# 03-LED-GREEN.net
KiCad netlist of a schematic drawn in Altium Designer
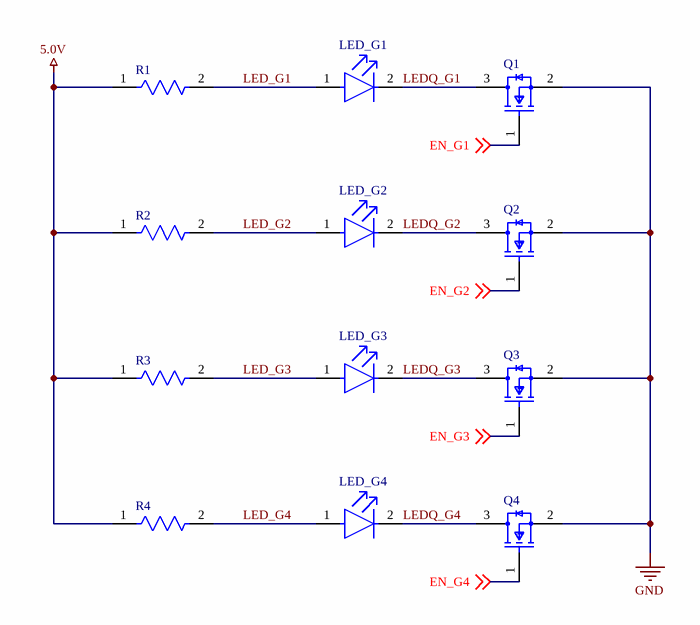
[diagram p0: 03-LED-GREEN.SchDoc]

(export (version "E")
  (design (tool "Eeschema 10.0.6"))
  (components
    (comp (ref "LED_G1")
      (value "SML-LX1206GC-TR")
      (footprint "FP-SML-LX1206GC-TR-MFG")
      (description "LED GREEN CLEAR 1206 SMD")
      (libsource (lib "Altium Content Vault") (part "ab1c01a81903e929fc6c44469aada92"))
    )
    (comp (ref "LED_G2")
      (value "SML-LX1206GC-TR")
      (footprint "FP-SML-LX1206GC-TR-MFG")
      (description "LED GREEN CLEAR 1206 SMD")
      (libsource (lib "Altium Content Vault") (part "ab1c01a81903e929fc6c44469aada92"))
    )
    (comp (ref "LED_G3")
      (value "SML-LX1206GC-TR")
      (footprint "FP-SML-LX1206GC-TR-MFG")
      (description "LED GREEN CLEAR 1206 SMD")
      (libsource (lib "Altium Content Vault") (part "ab1c01a81903e929fc6c44469aada92"))
    )
    (comp (ref "LED_G4")
      (value "SML-LX1206GC-TR")
      (footprint "FP-SML-LX1206GC-TR-MFG")
      (description "LED GREEN CLEAR 1206 SMD")
      (libsource (lib "Altium Content Vault") (part "ab1c01a81903e929fc6c44469aada92"))
    )
    (comp (ref "Q1")
      (value "2N7002-7-F")
      (footprint "FP-SOT23-MFG")
      (description "MOSFET N-CH 60V 115MA SOT23-3")
      (fields (field (name "VOLTAGE") "60V"))
      (libsource (lib "Altium Content Vault") (part "3b9c635fedb024a5347a57b145af9cc"))
    )
    (comp (ref "Q2")
      (value "2N7002-7-F")
      (footprint "FP-SOT23-MFG")
      (description "MOSFET N-CH 60V 115MA SOT23-3")
      (fields (field (name "VOLTAGE") "60V"))
      (libsource (lib "Altium Content Vault") (part "3b9c635fedb024a5347a57b145af9cc"))
    )
    (comp (ref "Q3")
      (value "2N7002-7-F")
      (footprint "FP-SOT23-MFG")
      (description "MOSFET N-CH 60V 115MA SOT23-3")
      (fields (field (name "VOLTAGE") "60V"))
      (libsource (lib "Altium Content Vault") (part "3b9c635fedb024a5347a57b145af9cc"))
    )
    (comp (ref "Q4")
      (value "2N7002-7-F")
      (footprint "FP-SOT23-MFG")
      (description "MOSFET N-CH 60V 115MA SOT23-3")
      (fields (field (name "VOLTAGE") "60V"))
      (libsource (lib "Altium Content Vault") (part "3b9c635fedb024a5347a57b145af9cc"))
    )
    (comp (ref "R1")
      (value "CRCW1206330RFKEA")
      (footprint "FP-CRCW1206-e3-IPC_A")
      (description "RES Thick Film, 330Ω, 1%, 0.25W, 100ppm/°C, 1206")
      (fields (field (name "TOLERANCE") "1%"))
      (libsource (lib "Altium Content Vault") (part "1029c3af85768c4190bb7ad29bc67b5"))
    )
    (comp (ref "R2")
      (value "CRCW1206330RFKEA")
      (footprint "FP-CRCW1206-e3-IPC_A")
      (description "RES Thick Film, 330Ω, 1%, 0.25W, 100ppm/°C, 1206")
      (fields (field (name "TOLERANCE") "1%"))
      (libsource (lib "Altium Content Vault") (part "1029c3af85768c4190bb7ad29bc67b5"))
    )
    (comp (ref "R3")
      (value "CRCW1206330RFKEA")
      (footprint "FP-CRCW1206-e3-IPC_A")
      (description "RES Thick Film, 330Ω, 1%, 0.25W, 100ppm/°C, 1206")
      (fields (field (name "TOLERANCE") "1%"))
      (libsource (lib "Altium Content Vault") (part "1029c3af85768c4190bb7ad29bc67b5"))
    )
    (comp (ref "R4")
      (value "CRCW1206330RFKEA")
      (footprint "FP-CRCW1206-e3-IPC_A")
      (description "RES Thick Film, 330Ω, 1%, 0.25W, 100ppm/°C, 1206")
      (fields (field (name "TOLERANCE") "1%"))
      (libsource (lib "Altium Content Vault") (part "1029c3af85768c4190bb7ad29bc67b5"))
    )
  )
  (nets
    (net (code "1") (name "/LEDQ_G1") (class "Default")
      (node (ref "LED_G1") (pin "2") (pinfunction "C_2") (pintype "passive"))
      (node (ref "Q1") (pin "3") (pinfunction "D_3") (pintype "passive"))
    )
    (net (code "2") (name "/LEDQ_G2") (class "Default")
      (node (ref "LED_G2") (pin "2") (pinfunction "C_2") (pintype "passive"))
      (node (ref "Q2") (pin "3") (pinfunction "D_3") (pintype "passive"))
    )
    (net (code "3") (name "/LEDQ_G3") (class "Default")
      (node (ref "LED_G3") (pin "2") (pinfunction "C_2") (pintype "passive"))
      (node (ref "Q3") (pin "3") (pinfunction "D_3") (pintype "passive"))
    )
    (net (code "4") (name "/LEDQ_G4") (class "Default")
      (node (ref "LED_G4") (pin "2") (pinfunction "C_2") (pintype "passive"))
      (node (ref "Q4") (pin "3") (pinfunction "D_3") (pintype "passive"))
    )
    (net (code "5") (name "/LED_G1") (class "Default")
      (node (ref "LED_G1") (pin "1") (pinfunction "A_1") (pintype "passive"))
      (node (ref "R1") (pin "2") (pinfunction "2_2") (pintype "passive"))
    )
    (net (code "6") (name "/LED_G2") (class "Default")
      (node (ref "LED_G2") (pin "1") (pinfunction "A_1") (pintype "passive"))
      (node (ref "R2") (pin "2") (pinfunction "2_2") (pintype "passive"))
    )
    (net (code "7") (name "/LED_G3") (class "Default")
      (node (ref "LED_G3") (pin "1") (pinfunction "A_1") (pintype "passive"))
      (node (ref "R3") (pin "2") (pinfunction "2_2") (pintype "passive"))
    )
    (net (code "8") (name "/LED_G4") (class "Default")
      (node (ref "LED_G4") (pin "1") (pinfunction "A_1") (pintype "passive"))
      (node (ref "R4") (pin "2") (pinfunction "2_2") (pintype "passive"))
    )
    (net (code "9") (name "5.0V") (class "Default")
      (node (ref "R1") (pin "1") (pinfunction "1_1") (pintype "passive"))
      (node (ref "R2") (pin "1") (pinfunction "1_1") (pintype "passive"))
      (node (ref "R3") (pin "1") (pinfunction "1_1") (pintype "passive"))
      (node (ref "R4") (pin "1") (pinfunction "1_1") (pintype "passive"))
    )
    (net (code "10") (name "EN_G1") (class "Default")
      (node (ref "Q1") (pin "1") (pinfunction "G_1") (pintype "passive"))
    )
    (net (code "11") (name "EN_G2") (class "Default")
      (node (ref "Q2") (pin "1") (pinfunction "G_1") (pintype "passive"))
    )
    (net (code "12") (name "EN_G3") (class "Default")
      (node (ref "Q3") (pin "1") (pinfunction "G_1") (pintype "passive"))
    )
    (net (code "13") (name "EN_G4") (class "Default")
      (node (ref "Q4") (pin "1") (pinfunction "G_1") (pintype "passive"))
    )
    (net (code "14") (name "GND") (class "Default")
      (node (ref "Q1") (pin "2") (pinfunction "S_2") (pintype "passive"))
      (node (ref "Q2") (pin "2") (pinfunction "S_2") (pintype "passive"))
      (node (ref "Q3") (pin "2") (pinfunction "S_2") (pintype "passive"))
      (node (ref "Q4") (pin "2") (pinfunction "S_2") (pintype "passive"))
    )
  )
)
